# V1_0.net
KiCad netlist of a schematic drawn in Altium Designer
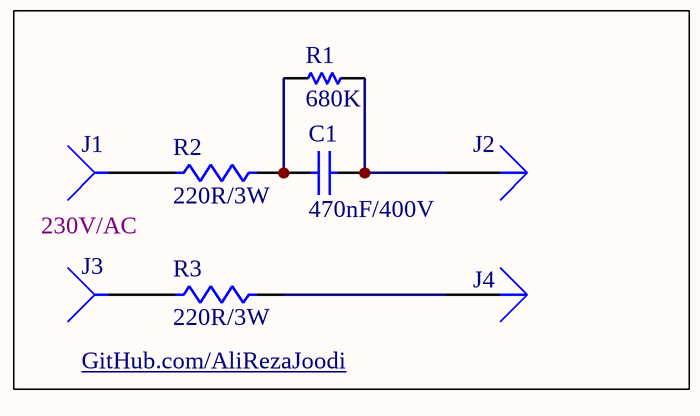
[diagram p0: V1.0.SchDoc]

(export (version "E")
  (design (tool "Eeschema 10.0.6"))
  (components
    (comp (ref "C1")
      (value "470nF/400V")
      (footprint "C_THD_CER_(P5.08-D8-T3)")
      (description "Capacitor, Ceramic Multilayer")
      (libsource (lib "Passive") (part "Capacitor_Ceramic"))
    )
    (comp (ref "J1")
      (value "1PIN")
      (description "Connector, Socket, 1Pin")
      (libsource (lib "Connector") (part "Connector_Socket_1Pin_Female"))
    )
    (comp (ref "J2")
      (value "1PIN")
      (description "Connector, Socket, 1Pin")
      (libsource (lib "Connector") (part "Connector_Socket_1Pin_Male"))
    )
    (comp (ref "J3")
      (value "1PIN")
      (description "Connector, Socket, 1Pin")
      (libsource (lib "Connector") (part "Connector_Socket_1Pin_Female"))
    )
    (comp (ref "J4")
      (value "1PIN")
      (description "Connector, Socket, 1Pin")
      (libsource (lib "Connector") (part "Connector_Socket_1Pin_Male"))
    )
    (comp (ref "R1")
      (value "680K")
      (footprint "R_THD_AXIAL0.4(1/4W)")
      (description "Resistor")
      (libsource (lib "Passive") (part "Resistor"))
    )
    (comp (ref "R2")
      (value "220R/3W")
      (footprint "R_THD_AXIAL0.9(3W)")
      (description "Resistor")
      (libsource (lib "Passive") (part "Resistor_2Form"))
    )
    (comp (ref "R3")
      (value "220R/3W")
      (footprint "R_THD_AXIAL0.9(3W)")
      (description "Resistor")
      (libsource (lib "Passive") (part "Resistor_2Form"))
    )
  )
  (nets
    (net (code "1") (name "Net-(C1-Pad1)") (class "Default")
      (node (ref "C1") (pin "1") (pinfunction "1_1") (pintype "passive"))
      (node (ref "R1") (pin "1") (pinfunction "1_1") (pintype "passive"))
      (node (ref "R2") (pin "2") (pinfunction "2_2") (pintype "passive"))
    )
    (net (code "2") (name "Net-(J1-A)") (class "Default")
      (node (ref "J1") (pin "1") (pinfunction "A_1") (pintype "passive"))
      (node (ref "R2") (pin "1") (pinfunction "1_1") (pintype "passive"))
    )
    (net (code "3") (name "Net-(J2-A)") (class "Default")
      (node (ref "C1") (pin "2") (pinfunction "2_2") (pintype "passive"))
      (node (ref "J2") (pin "1") (pinfunction "A_1") (pintype "passive"))
      (node (ref "R1") (pin "2") (pinfunction "2_2") (pintype "passive"))
    )
    (net (code "4") (name "Net-(J3-A)") (class "Default")
      (node (ref "J3") (pin "1") (pinfunction "A_1") (pintype "passive"))
      (node (ref "R3") (pin "1") (pinfunction "1_1") (pintype "passive"))
    )
    (net (code "5") (name "Net-(J4-A)") (class "Default")
      (node (ref "J4") (pin "1") (pinfunction "A_1") (pintype "passive"))
      (node (ref "R3") (pin "2") (pinfunction "2_2") (pintype "passive"))
    )
  )
)
